# SparkFun_Qwiic_FS3000_TEE.net
KiCad netlist of a schematic drawn in EAGLE
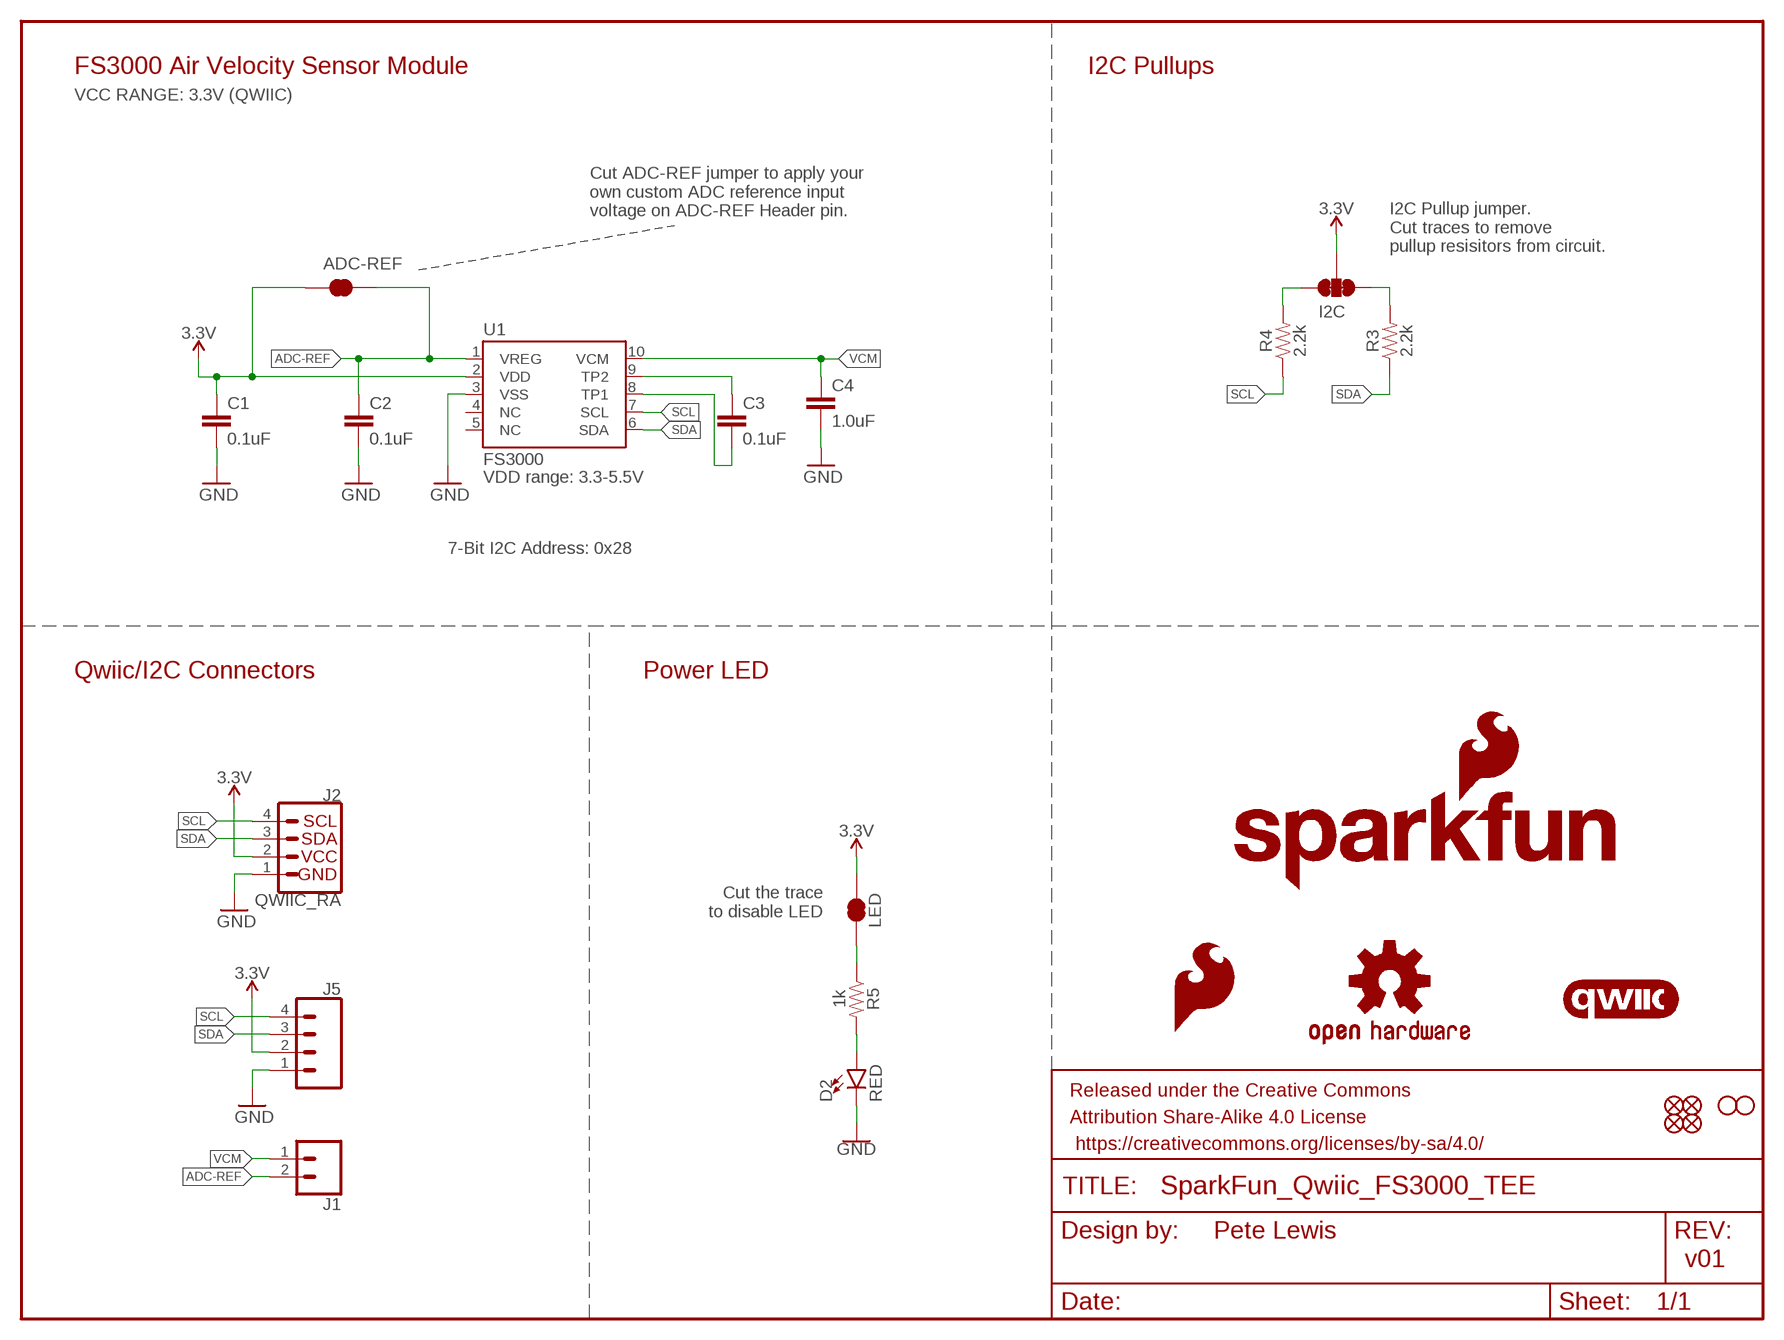
[diagram p0: schematic, sheet 1]

(export (version "E")
  (design (tool "Eeschema 10.0.6"))
  (components
    (comp (ref "ADC-REF")
      (value "JUMPER-SMT_2_NC_TRACE_SILK")
      (footprint "eagle-import:SMT-JUMPER_2_NC_TRACE_SILK")
      (libsource (lib "eagle-import") (part "JUMPER-SMT_2_NC_TRACE_SILK"))
    )
    (comp (ref "C1")
      (value "0.1uF")
      (footprint "eagle-import:0402-TIGHT")
      (libsource (lib "eagle-import") (part "0.1UF-0402T-16V-10%"))
    )
    (comp (ref "C2")
      (value "0.1uF")
      (footprint "eagle-import:0402-TIGHT")
      (libsource (lib "eagle-import") (part "0.1UF-0402T-16V-10%"))
    )
    (comp (ref "C3")
      (value "0.1uF")
      (footprint "eagle-import:0402-TIGHT")
      (libsource (lib "eagle-import") (part "0.1UF-0402T-16V-10%"))
    )
    (comp (ref "C4")
      (value "1.0uF")
      (footprint "eagle-import:0402-TIGHT")
      (libsource (lib "eagle-import") (part "1.0UF-0402T-16V-10%"))
    )
    (comp (ref "D2")
      (value "RED")
      (footprint "eagle-import:LED-0603")
      (libsource (lib "eagle-import") (part "LED-RED0603"))
    )
    (comp (ref "FRAME1")
      (value "FRAME-LETTER")
      (footprint "eagle-import:CREATIVE_COMMONS")
      (libsource (lib "eagle-import") (part "FRAME-LETTER"))
    )
    (comp (ref "I2C")
      (value "JUMPER-SMT_3_2-NC_TRACE_SILK")
      (footprint "eagle-import:SMT-JUMPER_3_2-NC_TRACE_SILK")
      (libsource (lib "eagle-import") (part "JUMPER-SMT_3_2-NC_TRACE_SILK"))
    )
    (comp (ref "J1")
      (value "CONN_021X02_NO_SILK")
      (footprint "eagle-import:1X02_NO_SILK")
      (libsource (lib "eagle-import") (part "CONN_021X02_NO_SILK"))
    )
    (comp (ref "J2")
      (value "QWIIC_RA")
      (footprint "eagle-import:JST04_1MM_RA")
      (libsource (lib "eagle-import") (part "QWIIC_CONNECTORJS-1MM"))
    )
    (comp (ref "J5")
      (value "CONN_041X04_NO_SILK")
      (footprint "eagle-import:1X04_NO_SILK")
      (libsource (lib "eagle-import") (part "CONN_041X04_NO_SILK"))
    )
    (comp (ref "JP1")
      (value "LED")
      (footprint "eagle-import:SMT-JUMPER_2_NC_TRACE_SILK")
      (libsource (lib "eagle-import") (part "JUMPER-SMT_2_NC_TRACE_SILK"))
    )
    (comp (ref "JP2")
      (value "FIDUCIALUFIDUCIAL")
      (footprint "eagle-import:FIDUCIAL-MICRO")
      (libsource (lib "eagle-import") (part "FIDUCIALUFIDUCIAL"))
    )
    (comp (ref "JP3")
      (value "STAND-OFF")
      (footprint "eagle-import:STAND-OFF")
      (libsource (lib "eagle-import") (part "STAND-OFF"))
    )
    (comp (ref "JP5")
      (value "FIDUCIALUFIDUCIAL")
      (footprint "eagle-import:FIDUCIAL-MICRO")
      (libsource (lib "eagle-import") (part "FIDUCIALUFIDUCIAL"))
    )
    (comp (ref "JP6")
      (value "FIDUCIALUFIDUCIAL")
      (footprint "eagle-import:FIDUCIAL-MICRO")
      (libsource (lib "eagle-import") (part "FIDUCIALUFIDUCIAL"))
    )
    (comp (ref "JP8")
      (value "STAND-OFF")
      (footprint "eagle-import:STAND-OFF")
      (libsource (lib "eagle-import") (part "STAND-OFF"))
    )
    (comp (ref "JP11")
      (value "FIDUCIALUFIDUCIAL")
      (footprint "eagle-import:FIDUCIAL-MICRO")
      (libsource (lib "eagle-import") (part "FIDUCIALUFIDUCIAL"))
    )
    (comp (ref "LOGO1")
      (value "OSHW-LOGOMINI")
      (footprint "eagle-import:OSHW-LOGO-MINI")
      (libsource (lib "eagle-import") (part "OSHW-LOGOMINI"))
    )
    (comp (ref "LOGO3")
      (value "SFE_LOGO_FLAME.1_INCH")
      (footprint "eagle-import:SFE_LOGO_FLAME_.1")
      (libsource (lib "eagle-import") (part "SFE_LOGO_FLAME.1_INCH"))
    )
    (comp (ref "LOGO4")
      (value "QWIIC_LOGO_5MM")
      (footprint "eagle-import:QWIIC_5MM")
      (libsource (lib "eagle-import") (part "QWIIC_LOGO_5MM"))
    )
    (comp (ref "LOGO5")
      (value "SFE_LOGO_NAME_FLAME.1_INCH")
      (footprint "eagle-import:SFE_LOGO_NAME_FLAME_.1")
      (libsource (lib "eagle-import") (part "SFE_LOGO_NAME_FLAME.1_INCH"))
    )
    (comp (ref "R3")
      (value "2.2k")
      (footprint "eagle-import:0402-TIGHT")
      (libsource (lib "eagle-import") (part "2.2KOHM-0402T-1/16W-1%"))
    )
    (comp (ref "R4")
      (value "2.2k")
      (footprint "eagle-import:0402-TIGHT")
      (libsource (lib "eagle-import") (part "2.2KOHM-0402T-1/16W-1%"))
    )
    (comp (ref "R5")
      (value "1k")
      (footprint "eagle-import:0402-TIGHT")
      (libsource (lib "eagle-import") (part "1KOHM-0402T-1/16W-1%"))
    )
    (comp (ref "U1")
      (value "FS3000")
      (footprint "eagle-import:FS3000")
      (libsource (lib "eagle-import") (part "FS3000"))
    )
  )
  (nets
    (net (code "1") (name "3.3V") (class "Default")
      (node (ref "ADC-REF") (pin "1") (pinfunction "1_1") (pintype "passive"))
      (node (ref "C1") (pin "1") (pinfunction "1_1") (pintype "passive"))
      (node (ref "I2C") (pin "2") (pinfunction "2_2") (pintype "passive"))
      (node (ref "J2") (pin "2") (pinfunction "2_2") (pintype "power_in"))
      (node (ref "J5") (pin "2") (pinfunction "2_2") (pintype "passive"))
      (node (ref "JP1") (pin "2") (pinfunction "2_2") (pintype "passive"))
      (node (ref "U1") (pin "2") (pinfunction "VDD_2") (pintype "bidirectional"))
    )
    (net (code "2") (name "ADC-REF") (class "Default")
      (node (ref "ADC-REF") (pin "2") (pinfunction "2_2") (pintype "passive"))
      (node (ref "C2") (pin "1") (pinfunction "1_1") (pintype "passive"))
      (node (ref "J1") (pin "2") (pinfunction "2_2") (pintype "passive"))
      (node (ref "U1") (pin "1") (pinfunction "VREG_1") (pintype "bidirectional"))
    )
    (net (code "3") (name "GND") (class "Default")
      (node (ref "C1") (pin "2") (pinfunction "2_2") (pintype "passive"))
      (node (ref "C2") (pin "2") (pinfunction "2_2") (pintype "passive"))
      (node (ref "C4") (pin "2") (pinfunction "2_2") (pintype "passive"))
      (node (ref "D2") (pin "C") (pinfunction "C_C") (pintype "passive"))
      (node (ref "J2") (pin "1") (pinfunction "1_1") (pintype "power_in"))
      (node (ref "J5") (pin "1") (pinfunction "1_1") (pintype "passive"))
      (node (ref "U1") (pin "3") (pinfunction "VSS_3") (pintype "bidirectional"))
    )
    (net (code "4") (name "Net-(D2-PadA)") (class "Default")
      (node (ref "D2") (pin "A") (pinfunction "A_A") (pintype "passive"))
      (node (ref "R5") (pin "2") (pinfunction "2_2") (pintype "passive"))
    )
    (net (code "5") (name "Net-(I2C-Pad1)") (class "Default")
      (node (ref "I2C") (pin "1") (pinfunction "1_1") (pintype "passive"))
      (node (ref "R3") (pin "2") (pinfunction "2_2") (pintype "passive"))
    )
    (net (code "6") (name "Net-(I2C-Pad3)") (class "Default")
      (node (ref "I2C") (pin "3") (pinfunction "3_3") (pintype "passive"))
      (node (ref "R4") (pin "2") (pinfunction "2_2") (pintype "passive"))
    )
    (net (code "7") (name "Net-(JP1-Pad1)") (class "Default")
      (node (ref "JP1") (pin "1") (pinfunction "1_1") (pintype "passive"))
      (node (ref "R5") (pin "1") (pinfunction "1_1") (pintype "passive"))
    )
    (net (code "8") (name "Net-(U1-TP1)") (class "Default")
      (node (ref "C3") (pin "2") (pinfunction "2_2") (pintype "passive"))
      (node (ref "U1") (pin "8") (pinfunction "TP1_8") (pintype "bidirectional"))
    )
    (net (code "9") (name "Net-(U1-TP2)") (class "Default")
      (node (ref "C3") (pin "1") (pinfunction "1_1") (pintype "passive"))
      (node (ref "U1") (pin "9") (pinfunction "TP2_9") (pintype "bidirectional"))
    )
    (net (code "10") (name "SCL") (class "Default")
      (node (ref "J2") (pin "4") (pinfunction "4_4") (pintype "passive"))
      (node (ref "J5") (pin "4") (pinfunction "4_4") (pintype "passive"))
      (node (ref "R4") (pin "1") (pinfunction "1_1") (pintype "passive"))
      (node (ref "U1") (pin "7") (pinfunction "SCL_7") (pintype "bidirectional"))
    )
    (net (code "11") (name "SDA") (class "Default")
      (node (ref "J2") (pin "3") (pinfunction "3_3") (pintype "passive"))
      (node (ref "J5") (pin "3") (pinfunction "3_3") (pintype "passive"))
      (node (ref "R3") (pin "1") (pinfunction "1_1") (pintype "passive"))
      (node (ref "U1") (pin "6") (pinfunction "SDA_6") (pintype "bidirectional"))
    )
    (net (code "12") (name "VCM") (class "Default")
      (node (ref "C4") (pin "1") (pinfunction "1_1") (pintype "passive"))
      (node (ref "J1") (pin "1") (pinfunction "1_1") (pintype "passive"))
      (node (ref "U1") (pin "10") (pinfunction "VCM_10") (pintype "bidirectional"))
    )
    (net (code "13") (name "unconnected-(U1-NC-Pad4)") (class "Default")
      (node (ref "U1") (pin "4") (pinfunction "NC_4") (pintype "no_connect"))
    )
    (net (code "14") (name "unconnected-(U1-NC-Pad5)") (class "Default")
      (node (ref "U1") (pin "5") (pinfunction "NC_5") (pintype "no_connect"))
    )
  )
)
